# adapter.net
KiCad netlist of a schematic drawn in Altium Designer
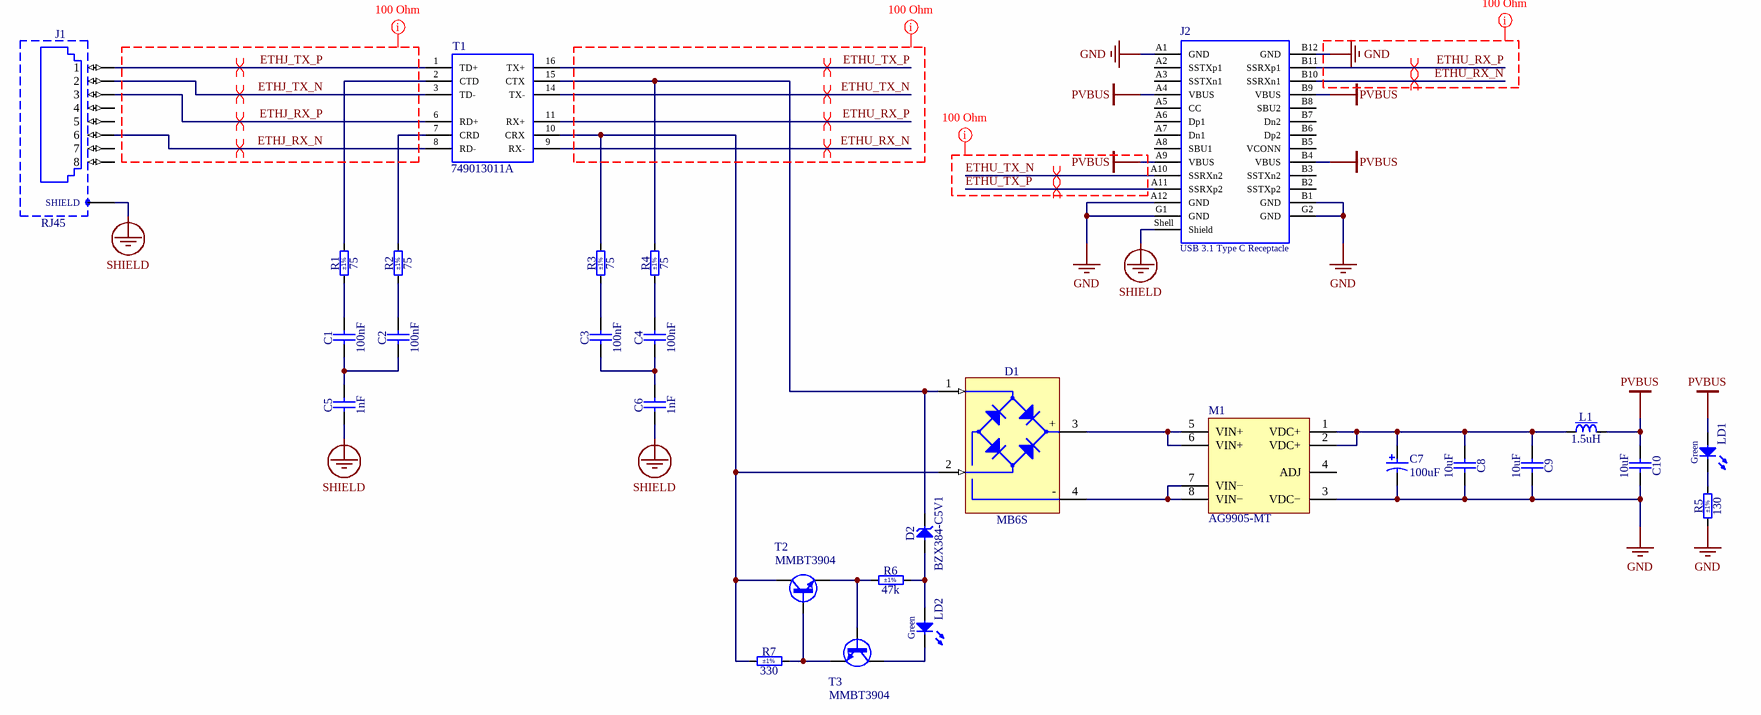
[diagram p0: adapter.SchDoc]

(export (version "E")
  (design (tool "Eeschema 10.0.6"))
  (components
    (comp (ref "C1")
      (value "100nF")
      (footprint "CAPC1608X90N")
      (description "Non-polarised capacitor")
      (fields
        (field (name "PART NUMBER") "CC0603_100NF_100V_10%_X7R")
        (field (name "VOLTAGE") "100V")
        (field (name "AUTHOR") "CERN DEM JLC")
      )
      (libsource (lib "Capacitors") (part "Capacitor - non polarized"))
    )
    (comp (ref "C2")
      (value "100nF")
      (footprint "CAPC1608X90N")
      (description "Non-polarised capacitor")
      (fields
        (field (name "PART NUMBER") "CC0603_100NF_100V_10%_X7R")
        (field (name "VOLTAGE") "100V")
        (field (name "AUTHOR") "CERN DEM JLC")
      )
      (libsource (lib "Capacitors") (part "Capacitor - non polarized"))
    )
    (comp (ref "C3")
      (value "100nF")
      (footprint "CAPC1608X90N")
      (description "Non-polarised capacitor")
      (fields
        (field (name "PART NUMBER") "CC0603_100NF_100V_10%_X7R")
        (field (name "VOLTAGE") "100V")
        (field (name "AUTHOR") "CERN DEM JLC")
      )
      (libsource (lib "Capacitors") (part "Capacitor - non polarized"))
    )
    (comp (ref "C4")
      (value "100nF")
      (footprint "CAPC1608X90N")
      (description "Non-polarised capacitor")
      (fields
        (field (name "PART NUMBER") "CC0603_100NF_100V_10%_X7R")
        (field (name "VOLTAGE") "100V")
        (field (name "AUTHOR") "CERN DEM JLC")
      )
      (libsource (lib "Capacitors") (part "Capacitor - non polarized"))
    )
    (comp (ref "C5")
      (value "1nF")
      (footprint "CAPC3216X180N")
      (description "Non-polarised capacitor")
      (fields
        (field (name "PART NUMBER") "CC1206_1NF_2KV_10%_X7R")
        (field (name "VOLTAGE") "2kV")
        (field (name "AUTHOR") "CERN DEM JLC")
      )
      (libsource (lib "Capacitors") (part "Capacitor - non polarized"))
    )
    (comp (ref "C6")
      (value "1nF")
      (footprint "CAPC3216X180N")
      (description "Non-polarised capacitor")
      (fields
        (field (name "PART NUMBER") "CC1206_1NF_2KV_10%_X7R")
        (field (name "VOLTAGE") "2kV")
        (field (name "AUTHOR") "CERN DEM JLC")
      )
      (libsource (lib "Capacitors") (part "Capacitor - non polarized"))
    )
    (comp (ref "C7")
      (value "100uF")
      (footprint "PNSC-EEEFK1C101P_L")
      (fields (field (name "MANUFACTURER") "Panasonic"))
      (libsource (lib "Altium Content Vault") (part "CAP-P-2"))
    )
    (comp (ref "C8")
      (value "10uF")
      (footprint "CAPC3225X270N")
      (description "Non-polarised capacitor")
      (fields
        (field (name "PART NUMBER") "CC1210_10UF_25V_10%_X7R")
        (field (name "VOLTAGE") "25V")
        (field (name "AUTHOR") "CERN DEM JLC")
      )
      (libsource (lib "Capacitors") (part "Capacitor - non polarized"))
    )
    (comp (ref "C9")
      (value "10uF")
      (footprint "CAPC3225X270N")
      (description "Non-polarised capacitor")
      (fields
        (field (name "PART NUMBER") "CC1210_10UF_25V_10%_X7R")
        (field (name "VOLTAGE") "25V")
        (field (name "AUTHOR") "CERN DEM JLC")
      )
      (libsource (lib "Capacitors") (part "Capacitor - non polarized"))
    )
    (comp (ref "C10")
      (value "10uF")
      (footprint "CAPC3225X270N")
      (description "Non-polarised capacitor")
      (fields
        (field (name "PART NUMBER") "CC1210_10UF_25V_10%_X7R")
        (field (name "VOLTAGE") "25V")
        (field (name "AUTHOR") "CERN DEM JLC")
      )
      (libsource (lib "Capacitors") (part "Capacitor - non polarized"))
    )
    (comp (ref "D1")
      (value "MB6S")
      (footprint "SOIC254P665X290-4N")
      (description "Bridge Rectifier 1AC 2AC 3+ 4-")
      (fields
        (field (name "VOLTAGE") "600V")
        (field (name "POWER") "0.5A")
        (field (name "AUTHOR") "CERN DEM MR")
      )
      (libsource (lib "ICs And Semiconductors") (part "Bridge Rectifier 1AC 2AC 3+ 4-"))
    )
    (comp (ref "D2")
      (value "BZX384-C5V1")
      (footprint "SOD2512X110N")
      (description "Zener Diode")
      (fields
        (field (name "VOLTAGE") "5.1V")
        (field (name "POWER") "300mW")
        (field (name "AUTHOR") "CERN DEM MR")
      )
      (libsource (lib "ICs And Semiconductors") (part "Diode Zener"))
    )
    (comp (ref "J1")
      (value "RJ45")
      (footprint "MOLEX_44661-1001")
      (description "Connector RJ45 + Shield")
      (fields
        (field (name "PART NUMBER") "MOLEX_44661-1001")
        (field (name "MANUFACTURER") "MOLEX")
        (field (name "AUTHOR") "CERN DEM BC")
      )
      (libsource (lib "Connectors") (part "Connector RJ45 + Shield"))
    )
    (comp (ref "J2")
      (value "USB 3.1 Type C Receptacle")
      (footprint "632723300011")
      (description "USB 3.1 Type C, Receptacle, Horizontal, THR")
      (fields
        (field (name "MANUFACTURER") "Wurth Elektronik")
        (field (name "MANUFACTURER PART NUMBER") "632723300011")
      )
      (libsource (lib "WR-USB_USB 3.1") (part "632723300011"))
    )
    (comp (ref "L1")
      (value "1.5uH")
      (footprint "IND_COILCRAFT_1812CS")
      (description "Inductor With Core")
      (fields
        (field (name "PART NUMBER") "IND_1.5UH_2%_COILCRAFT_1812CS")
        (field (name "POWER") "430mA")
        (field (name "AUTHOR") "CERN DEM JMW")
      )
      (libsource (lib "Inductors & Transformers") (part "Inductor With Magnetic core"))
    )
    (comp (ref "LD1")
      (value "Green")
      (footprint "LED_LITEON_LTST-C193KGKT-5A")
      (description "LED Green 1C 2A")
      (fields
        (field (name "PART NUMBER") "LED_LITEON_LTST-C193KGKT-5A")
        (field (name "MANUFACTURER") "LITE-ON SEMICONDUCTOR")
        (field (name "AUTHOR") "CERN DEM BC")
      )
      (libsource (lib "ICs And Semiconductors") (part "LED Green 1C 2A"))
    )
    (comp (ref "LD2")
      (value "Green")
      (footprint "LED_LITEON_LTST-C193KGKT-5A")
      (description "LED Green 1C 2A")
      (fields
        (field (name "PART NUMBER") "LED_LITEON_LTST-C193KGKT-5A")
        (field (name "MANUFACTURER") "LITE-ON SEMICONDUCTOR")
        (field (name "AUTHOR") "CERN DEM BC")
      )
      (libsource (lib "ICs And Semiconductors") (part "LED Green 1C 2A"))
    )
    (comp (ref "M1")
      (value "AG9905-MT")
      (footprint "SILVERTEL_AG9900")
      (description "Ultra Miniature PoE, 5V, w/Thermal Protection")
      (fields (field (name "MANUFACTURER") "Silvertel"))
      (libsource (lib "DiPho") (part "AG9905-MT"))
    )
    (comp (ref "R1")
      (value "75")
      (footprint "RESC1608X55N")
      (description "Resistor - 1%")
      (fields
        (field (name "TOLERANCE") "±1%")
        (field (name "PART NUMBER") "R0603_75R_1%_0.1W_100PPM")
        (field (name "POWER") "0.1W")
        (field (name "AUTHOR") "CERN DEM JLC")
      )
      (libsource (lib "Resistors") (part "Resistor - 1%"))
    )
    (comp (ref "R2")
      (value "75")
      (footprint "RESC1608X55N")
      (description "Resistor - 1%")
      (fields
        (field (name "TOLERANCE") "±1%")
        (field (name "PART NUMBER") "R0603_75R_1%_0.1W_100PPM")
        (field (name "POWER") "0.1W")
        (field (name "AUTHOR") "CERN DEM JLC")
      )
      (libsource (lib "Resistors") (part "Resistor - 1%"))
    )
    (comp (ref "R3")
      (value "75")
      (footprint "RESC1608X55N")
      (description "Resistor - 1%")
      (fields
        (field (name "TOLERANCE") "±1%")
        (field (name "PART NUMBER") "R0603_75R_1%_0.1W_100PPM")
        (field (name "POWER") "0.1W")
        (field (name "AUTHOR") "CERN DEM JLC")
      )
      (libsource (lib "Resistors") (part "Resistor - 1%"))
    )
    (comp (ref "R4")
      (value "75")
      (footprint "RESC1608X55N")
      (description "Resistor - 1%")
      (fields
        (field (name "TOLERANCE") "±1%")
        (field (name "PART NUMBER") "R0603_75R_1%_0.1W_100PPM")
        (field (name "POWER") "0.1W")
        (field (name "AUTHOR") "CERN DEM JLC")
      )
      (libsource (lib "Resistors") (part "Resistor - 1%"))
    )
    (comp (ref "R5")
      (value "130")
      (footprint "RESC1608X55N")
      (description "Resistor - 1%")
      (fields
        (field (name "TOLERANCE") "±1%")
        (field (name "PART NUMBER") "R0603_130R_1%_0.1W_100PPM")
        (field (name "POWER") "0.1W")
        (field (name "AUTHOR") "CERN DEM JLC")
      )
      (libsource (lib "Resistors") (part "Resistor - 1%"))
    )
    (comp (ref "R6")
      (value "47k")
      (footprint "RESC1608X55N")
      (description "Resistor - 1%")
      (fields
        (field (name "TOLERANCE") "±1%")
        (field (name "PART NUMBER") "R0603_47K_1%_0.1W_100PPM")
        (field (name "POWER") "0.1W")
        (field (name "AUTHOR") "CERN DEM JLC")
      )
      (libsource (lib "Resistors") (part "Resistor - 1%"))
    )
    (comp (ref "R7")
      (value "330")
      (footprint "RESC1608X55N")
      (description "Resistor - 1%")
      (fields
        (field (name "TOLERANCE") "±1%")
        (field (name "PART NUMBER") "R0603_330R_1%_0.1W_100PPM")
        (field (name "POWER") "0.1W")
        (field (name "AUTHOR") "CERN DEM JLC")
      )
      (libsource (lib "Resistors") (part "Resistor - 1%"))
    )
    (comp (ref "T1")
      (value "749013011A")
      (footprint "749013011A")
      (description "WE-LAN LAN Transformer, SMT, 10/100 Base-T, 1 port")
      (fields (field (name "MANUFACTURER") "Wurth Elektronik"))
      (libsource (lib "WE-LAN") (part "749013011A"))
    )
    (comp (ref "T2")
      (value "MMBT3904")
      (footprint "SOT95P230X110-3N")
      (description "NPN Transistor")
      (fields (field (name "MANUFACTURER") "NXP SEMICONDUCTORS") (field (name "AUTHOR") "CERN DEM JLC"))
      (libsource (lib "ICs And Semiconductors") (part "NPN B1 E2 C3"))
    )
    (comp (ref "T3")
      (value "MMBT3904")
      (footprint "SOT95P230X110-3N")
      (description "NPN Transistor")
      (fields (field (name "MANUFACTURER") "NXP SEMICONDUCTORS") (field (name "AUTHOR") "CERN DEM JLC"))
      (libsource (lib "ICs And Semiconductors") (part "NPN B1 E2 C3"))
    )
  )
  (nets
    (net (code "1") (name "/ETHJ_RX_N") (class "Default")
      (node (ref "J1") (pin "6") (pinfunction "6_6") (pintype "bidirectional"))
      (node (ref "T1") (pin "8") (pinfunction "RD-_8") (pintype "passive"))
    )
    (net (code "2") (name "/ETHJ_RX_P") (class "Default")
      (node (ref "J1") (pin "3") (pinfunction "3_3") (pintype "bidirectional"))
      (node (ref "T1") (pin "6") (pinfunction "RD+_6") (pintype "passive"))
    )
    (net (code "3") (name "/ETHJ_TX_N") (class "Default")
      (node (ref "J1") (pin "2") (pinfunction "2_2") (pintype "bidirectional"))
      (node (ref "T1") (pin "3") (pinfunction "TD-_3") (pintype "passive"))
    )
    (net (code "4") (name "/ETHJ_TX_P") (class "Default")
      (node (ref "J1") (pin "1") (pinfunction "1_1") (pintype "bidirectional"))
      (node (ref "T1") (pin "1") (pinfunction "TD+_1") (pintype "passive"))
    )
    (net (code "5") (name "/ETHU_RX_N") (class "Default")
      (node (ref "J2") (pin "B10") (pinfunction "SSRXn1_B10") (pintype "passive"))
      (node (ref "T1") (pin "9") (pinfunction "RX-_9") (pintype "passive"))
    )
    (net (code "6") (name "/ETHU_RX_P") (class "Default")
      (node (ref "J2") (pin "B11") (pinfunction "SSRXp1_B11") (pintype "passive"))
      (node (ref "T1") (pin "11") (pinfunction "RX+_11") (pintype "passive"))
    )
    (net (code "7") (name "/ETHU_TX_N") (class "Default")
      (node (ref "J2") (pin "A10") (pinfunction "SSRXn2_A10") (pintype "passive"))
      (node (ref "T1") (pin "14") (pinfunction "TX-_14") (pintype "passive"))
    )
    (net (code "8") (name "/ETHU_TX_P") (class "Default")
      (node (ref "J2") (pin "A11") (pinfunction "SSRXp2_A11") (pintype "passive"))
      (node (ref "T1") (pin "16") (pinfunction "TX+_16") (pintype "passive"))
    )
    (net (code "9") (name "GND") (class "Default")
      (node (ref "C10") (pin "2") (pinfunction "2_2") (pintype "passive"))
      (node (ref "C7") (pin "2") (pinfunction "2_2") (pintype "passive"))
      (node (ref "C8") (pin "2") (pinfunction "2_2") (pintype "passive"))
      (node (ref "C9") (pin "2") (pinfunction "2_2") (pintype "passive"))
      (node (ref "J2") (pin "A1") (pinfunction "GND_A1") (pintype "passive"))
      (node (ref "J2") (pin "A12") (pinfunction "GND_A12") (pintype "passive"))
      (node (ref "J2") (pin "B1") (pinfunction "GND_B1") (pintype "passive"))
      (node (ref "J2") (pin "B12") (pinfunction "GND_B12") (pintype "passive"))
      (node (ref "J2") (pin "G1") (pinfunction "GND_G1") (pintype "passive"))
      (node (ref "J2") (pin "G2") (pinfunction "GND_G2") (pintype "passive"))
      (node (ref "M1") (pin "3") (pinfunction "VDC−_3") (pintype "passive"))
      (node (ref "R5") (pin "1") (pinfunction "1_1") (pintype "passive"))
    )
    (net (code "10") (name "Net-(C1-Pad1)") (class "Default")
      (node (ref "C1") (pin "1") (pinfunction "1_1") (pintype "passive"))
      (node (ref "C2") (pin "1") (pinfunction "1_1") (pintype "passive"))
      (node (ref "C5") (pin "2") (pinfunction "2_2") (pintype "passive"))
    )
    (net (code "11") (name "Net-(C1-Pad2)") (class "Default")
      (node (ref "C1") (pin "2") (pinfunction "2_2") (pintype "passive"))
      (node (ref "R1") (pin "1") (pinfunction "1_1") (pintype "passive"))
    )
    (net (code "12") (name "Net-(C2-Pad2)") (class "Default")
      (node (ref "C2") (pin "2") (pinfunction "2_2") (pintype "passive"))
      (node (ref "R2") (pin "1") (pinfunction "1_1") (pintype "passive"))
    )
    (net (code "13") (name "Net-(C3-Pad1)") (class "Default")
      (node (ref "C3") (pin "1") (pinfunction "1_1") (pintype "passive"))
      (node (ref "C4") (pin "1") (pinfunction "1_1") (pintype "passive"))
      (node (ref "C6") (pin "2") (pinfunction "2_2") (pintype "passive"))
    )
    (net (code "14") (name "Net-(C3-Pad2)") (class "Default")
      (node (ref "C3") (pin "2") (pinfunction "2_2") (pintype "passive"))
      (node (ref "R3") (pin "1") (pinfunction "1_1") (pintype "passive"))
    )
    (net (code "15") (name "Net-(C4-Pad2)") (class "Default")
      (node (ref "C4") (pin "2") (pinfunction "2_2") (pintype "passive"))
      (node (ref "R4") (pin "1") (pinfunction "1_1") (pintype "passive"))
    )
    (net (code "16") (name "Net-(C7-Pad1)") (class "Default")
      (node (ref "C7") (pin "1") (pinfunction "1_1") (pintype "passive"))
      (node (ref "C8") (pin "1") (pinfunction "1_1") (pintype "passive"))
      (node (ref "C9") (pin "1") (pinfunction "1_1") (pintype "passive"))
      (node (ref "L1") (pin "1") (pinfunction "1_1") (pintype "passive"))
      (node (ref "M1") (pin "1") (pinfunction "VDC+_1") (pintype "passive"))
      (node (ref "M1") (pin "2") (pinfunction "VDC+_2") (pintype "passive"))
    )
    (net (code "17") (name "Net-(D1-+)") (class "Default")
      (node (ref "D1") (pin "3") (pinfunction "+_3") (pintype "power_in"))
      (node (ref "M1") (pin "5") (pinfunction "VIN+_5") (pintype "passive"))
      (node (ref "M1") (pin "6") (pinfunction "VIN+_6") (pintype "passive"))
    )
    (net (code "18") (name "Net-(D1--)") (class "Default")
      (node (ref "D1") (pin "4") (pinfunction "-_4") (pintype "power_in"))
      (node (ref "M1") (pin "7") (pinfunction "VIN−_7") (pintype "passive"))
      (node (ref "M1") (pin "8") (pinfunction "VIN−_8") (pintype "passive"))
    )
    (net (code "19") (name "Net-(D2-A)") (class "Default")
      (node (ref "D2") (pin "2") (pinfunction "A_2") (pintype "passive"))
      (node (ref "LD2") (pin "2") (pinfunction "A_2") (pintype "passive"))
      (node (ref "R6") (pin "2") (pinfunction "2_2") (pintype "passive"))
    )
    (net (code "20") (name "Net-(D2-C)") (class "Default")
      (node (ref "D1") (pin "1") (pinfunction "AC_1") (pintype "input"))
      (node (ref "D2") (pin "1") (pinfunction "C_1") (pintype "passive"))
      (node (ref "R4") (pin "2") (pinfunction "2_2") (pintype "passive"))
      (node (ref "T1") (pin "15") (pinfunction "CTX_15") (pintype "passive"))
    )
    (net (code "21") (name "Net-(LD1-C)") (class "Default")
      (node (ref "LD1") (pin "1") (pinfunction "C_1") (pintype "passive"))
      (node (ref "R5") (pin "2") (pinfunction "2_2") (pintype "passive"))
    )
    (net (code "22") (name "Net-(LD2-C)") (class "Default")
      (node (ref "LD2") (pin "1") (pinfunction "C_1") (pintype "passive"))
      (node (ref "T3") (pin "3") (pinfunction "C_3") (pintype "passive"))
    )
    (net (code "23") (name "Net-(T1-CRD)") (class "Default")
      (node (ref "R2") (pin "2") (pinfunction "2_2") (pintype "passive"))
      (node (ref "T1") (pin "7") (pinfunction "CRD_7") (pintype "passive"))
    )
    (net (code "24") (name "Net-(T1-CRX)") (class "Default")
      (node (ref "D1") (pin "2") (pinfunction "AC_2") (pintype "input"))
      (node (ref "R3") (pin "2") (pinfunction "2_2") (pintype "passive"))
      (node (ref "R7") (pin "1") (pinfunction "1_1") (pintype "passive"))
      (node (ref "T1") (pin "10") (pinfunction "CRX_10") (pintype "passive"))
      (node (ref "T2") (pin "3") (pinfunction "C_3") (pintype "passive"))
    )
    (net (code "25") (name "Net-(T1-CTD)") (class "Default")
      (node (ref "R1") (pin "2") (pinfunction "2_2") (pintype "passive"))
      (node (ref "T1") (pin "2") (pinfunction "CTD_2") (pintype "passive"))
    )
    (net (code "26") (name "Net-(T2-B)") (class "Default")
      (node (ref "R7") (pin "2") (pinfunction "2_2") (pintype "passive"))
      (node (ref "T2") (pin "1") (pinfunction "B_1") (pintype "passive"))
      (node (ref "T3") (pin "2") (pinfunction "E_2") (pintype "passive"))
    )
    (net (code "27") (name "Net-(T2-E)") (class "Default")
      (node (ref "R6") (pin "1") (pinfunction "1_1") (pintype "passive"))
      (node (ref "T2") (pin "2") (pinfunction "E_2") (pintype "passive"))
      (node (ref "T3") (pin "1") (pinfunction "B_1") (pintype "passive"))
    )
    (net (code "28") (name "PVBUS") (class "Default")
      (node (ref "C10") (pin "1") (pinfunction "1_1") (pintype "passive"))
      (node (ref "J2") (pin "A4") (pinfunction "VBUS_A4") (pintype "passive"))
      (node (ref "J2") (pin "A9") (pinfunction "VBUS_A9") (pintype "passive"))
      (node (ref "J2") (pin "B4") (pinfunction "VBUS_B4") (pintype "passive"))
      (node (ref "J2") (pin "B9") (pinfunction "VBUS_B9") (pintype "passive"))
      (node (ref "L1") (pin "2") (pinfunction "2_2") (pintype "passive"))
      (node (ref "LD1") (pin "2") (pinfunction "A_2") (pintype "passive"))
    )
    (net (code "29") (name "SHIELD") (class "Default")
      (node (ref "C5") (pin "1") (pinfunction "1_1") (pintype "passive"))
      (node (ref "C6") (pin "1") (pinfunction "1_1") (pintype "passive"))
      (node (ref "J1") (pin "SHIELD") (pinfunction "SHIELD_SHIELD") (pintype "passive"))
      (node (ref "J2") (pin "Shell") (pinfunction "Shield_Shell") (pintype "passive"))
    )
    (net (code "30") (name "unconnected-(J1-Pad4)") (class "Default")
      (node (ref "J1") (pin "4") (pinfunction "4_4") (pintype "bidirectional"))
    )
    (net (code "31") (name "unconnected-(J1-Pad5)") (class "Default")
      (node (ref "J1") (pin "5") (pinfunction "5_5") (pintype "bidirectional"))
    )
    (net (code "32") (name "unconnected-(J1-Pad7)") (class "Default")
      (node (ref "J1") (pin "7") (pinfunction "7_7") (pintype "bidirectional"))
    )
    (net (code "33") (name "unconnected-(J1-Pad8)") (class "Default")
      (node (ref "J1") (pin "8") (pinfunction "8_8") (pintype "bidirectional"))
    )
    (net (code "34") (name "unconnected-(J2-CC-PadA5)") (class "Default")
      (node (ref "J2") (pin "A5") (pinfunction "CC_A5") (pintype "passive"))
    )
    (net (code "35") (name "unconnected-(J2-Dn1-PadA7)") (class "Default")
      (node (ref "J2") (pin "A7") (pinfunction "Dn1_A7") (pintype "passive"))
    )
    (net (code "36") (name "unconnected-(J2-Dn2-PadB7)") (class "Default")
      (node (ref "J2") (pin "B7") (pinfunction "Dn2_B7") (pintype "passive"))
    )
    (net (code "37") (name "unconnected-(J2-Dp1-PadA6)") (class "Default")
      (node (ref "J2") (pin "A6") (pinfunction "Dp1_A6") (pintype "passive"))
    )
    (net (code "38") (name "unconnected-(J2-Dp2-PadB6)") (class "Default")
      (node (ref "J2") (pin "B6") (pinfunction "Dp2_B6") (pintype "passive"))
    )
    (net (code "39") (name "unconnected-(J2-SBU1-PadA8)") (class "Default")
      (node (ref "J2") (pin "A8") (pinfunction "SBU1_A8") (pintype "passive"))
    )
    (net (code "40") (name "unconnected-(J2-SBU2-PadB8)") (class "Default")
      (node (ref "J2") (pin "B8") (pinfunction "SBU2_B8") (pintype "passive"))
    )
    (net (code "41") (name "unconnected-(J2-SSTXn1-PadA3)") (class "Default")
      (node (ref "J2") (pin "A3") (pinfunction "SSTXn1_A3") (pintype "passive"))
    )
    (net (code "42") (name "unconnected-(J2-SSTXn2-PadB3)") (class "Default")
      (node (ref "J2") (pin "B3") (pinfunction "SSTXn2_B3") (pintype "passive"))
    )
    (net (code "43") (name "unconnected-(J2-SSTXp1-PadA2)") (class "Default")
      (node (ref "J2") (pin "A2") (pinfunction "SSTXp1_A2") (pintype "passive"))
    )
    (net (code "44") (name "unconnected-(J2-SSTXp2-PadB2)") (class "Default")
      (node (ref "J2") (pin "B2") (pinfunction "SSTXp2_B2") (pintype "passive"))
    )
    (net (code "45") (name "unconnected-(J2-VCONN-PadB5)") (class "Default")
      (node (ref "J2") (pin "B5") (pinfunction "VCONN_B5") (pintype "passive"))
    )
    (net (code "46") (name "unconnected-(M1-ADJ-Pad4)") (class "Default")
      (node (ref "M1") (pin "4") (pinfunction "ADJ_4") (pintype "passive"))
    )
  )
)
